# LM317_3S_LithiumCharger_2018_05_13.net
KiCad netlist of a schematic drawn in EAGLE
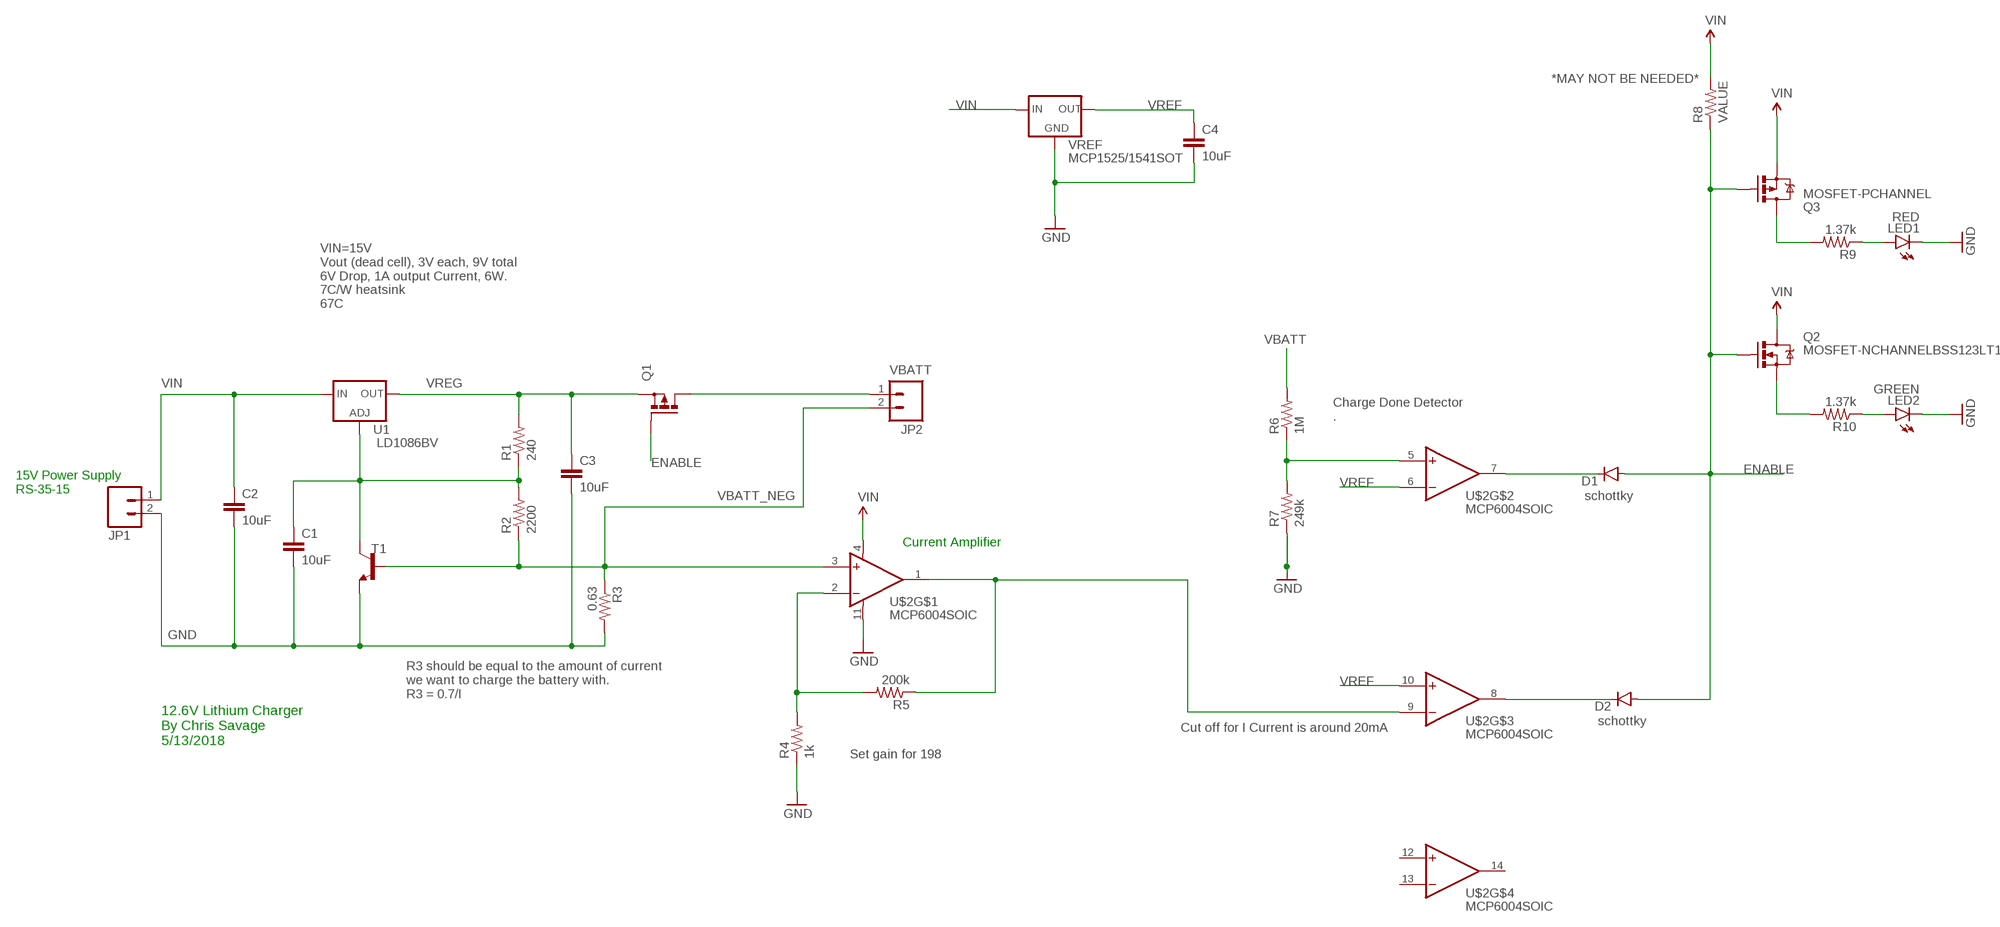
[diagram p0: schematic, sheet 1]

(export (version "E")
  (design (tool "Eeschema 10.0.6"))
  (components
    (comp (ref "C1")
      (value "10uF")
      (footprint "eagle-import:1206")
      (libsource (lib "eagle-import") (part "CAP1206"))
    )
    (comp (ref "C2")
      (value "10uF")
      (footprint "eagle-import:1206")
      (libsource (lib "eagle-import") (part "CAP1206"))
    )
    (comp (ref "C3")
      (value "10uF")
      (footprint "eagle-import:1206")
      (libsource (lib "eagle-import") (part "CAP1206"))
    )
    (comp (ref "C4")
      (value "10uF")
      (footprint "eagle-import:1206")
      (libsource (lib "eagle-import") (part "CAP1206"))
    )
    (comp (ref "D1")
      (value "DIODESOD123")
      (footprint "eagle-import:SOD-123")
      (libsource (lib "eagle-import") (part "DIODESOD123"))
    )
    (comp (ref "D2")
      (value "DIODESOD123")
      (footprint "eagle-import:SOD-123")
      (libsource (lib "eagle-import") (part "DIODESOD123"))
    )
    (comp (ref "JP1")
      (value "M02POLAR_LOCK")
      (footprint "eagle-import:MOLEX-1X2_LOCK")
      (libsource (lib "eagle-import") (part "M02POLAR_LOCK"))
    )
    (comp (ref "JP2")
      (value "M02POLAR_LOCK")
      (footprint "eagle-import:MOLEX-1X2_LOCK")
      (libsource (lib "eagle-import") (part "M02POLAR_LOCK"))
    )
    (comp (ref "LED1")
      (value "RED")
      (footprint "eagle-import:LED5MM")
      (libsource (lib "eagle-import") (part "LED5MM"))
    )
    (comp (ref "LED2")
      (value "GREEN")
      (footprint "eagle-import:LED5MM")
      (libsource (lib "eagle-import") (part "LED5MM"))
    )
    (comp (ref "Q1")
      (value "PMOSFET_PTO220BV")
      (footprint "eagle-import:TO220BV")
      (libsource (lib "eagle-import") (part "PMOSFET_PTO220BV"))
    )
    (comp (ref "Q2")
      (value "MOSFET-NCHANNELBSS123LT1G")
      (footprint "eagle-import:SOT23-3")
      (libsource (lib "eagle-import") (part "MOSFET-NCHANNELBSS123LT1G"))
    )
    (comp (ref "Q3")
      (value "MOSFET-PCHANNEL")
      (footprint "eagle-import:SOT23-3")
      (libsource (lib "eagle-import") (part "MOSFET-PCHANNEL"))
    )
    (comp (ref "R1")
      (value "240")
      (footprint "eagle-import:1206")
      (libsource (lib "eagle-import") (part "RESISTOR1206"))
    )
    (comp (ref "R2")
      (value "2200")
      (footprint "eagle-import:1206")
      (libsource (lib "eagle-import") (part "RESISTOR1206"))
    )
    (comp (ref "R3")
      (value "0.63")
      (footprint "eagle-import:R2512")
      (libsource (lib "eagle-import") (part "RESISTOR2512"))
    )
    (comp (ref "R4")
      (value "1k")
      (footprint "eagle-import:1206")
      (libsource (lib "eagle-import") (part "RESISTOR1206"))
    )
    (comp (ref "R5")
      (value "200k")
      (footprint "eagle-import:1206")
      (libsource (lib "eagle-import") (part "RESISTOR1206"))
    )
    (comp (ref "R6")
      (value "1M")
      (footprint "eagle-import:1206")
      (libsource (lib "eagle-import") (part "RESISTOR1206"))
    )
    (comp (ref "R7")
      (value "249k")
      (footprint "eagle-import:1206")
      (libsource (lib "eagle-import") (part "RESISTOR1206"))
    )
    (comp (ref "R8")
      (value "VALUE")
      (footprint "eagle-import:1206")
      (libsource (lib "eagle-import") (part "RESISTOR1206"))
    )
    (comp (ref "R9")
      (value "1.37k")
      (footprint "eagle-import:1206")
      (libsource (lib "eagle-import") (part "RESISTOR1206"))
    )
    (comp (ref "R10")
      (value "1.37k")
      (footprint "eagle-import:1206")
      (libsource (lib "eagle-import") (part "RESISTOR1206"))
    )
    (comp (ref "T1")
      (value "MMBT3904LT1-NPN-SOT23-BEC")
      (footprint "eagle-import:SOT23-BEC")
      (libsource (lib "eagle-import") (part "-NPN-SOT23-BECMMBT3904LT1"))
    )
    (comp (ref "U$2")
      (value "MCP6004SOIC")
      (footprint "eagle-import:SOIC-14")
      (libsource (lib "eagle-import") (part "MCP6004SOIC"))
    )
    (comp (ref "U1")
      (value "LD1086BV")
      (footprint "eagle-import:317TS")
      (libsource (lib "eagle-import") (part "LM317TS"))
    )
    (comp (ref "VREF")
      (value "MCP1525/1541SOT")
      (footprint "eagle-import:SOT23-3")
      (libsource (lib "eagle-import") (part "MCP1525/1541SOT"))
    )
  )
  (nets
    (net (code "1") (name "/ENABLE") (class "Default")
      (node (ref "D1") (pin "A") (pinfunction "A_A") (pintype "passive"))
      (node (ref "D2") (pin "A") (pinfunction "A_A") (pintype "passive"))
      (node (ref "Q1") (pin "G") (pinfunction "G_G") (pintype "passive"))
      (node (ref "Q2") (pin "1") (pinfunction "G_1") (pintype "passive"))
      (node (ref "Q3") (pin "1") (pinfunction "G_1") (pintype "passive"))
      (node (ref "R8") (pin "1") (pinfunction "1_1") (pintype "passive"))
    )
    (net (code "2") (name "/VBATT") (class "Default")
      (node (ref "JP2") (pin "1") (pinfunction "1_1") (pintype "passive"))
      (node (ref "Q1") (pin "D") (pinfunction "D_D") (pintype "passive"))
      (node (ref "R6") (pin "2") (pinfunction "2_2") (pintype "passive"))
    )
    (net (code "3") (name "/VBATT_NEG") (class "Default")
      (node (ref "JP2") (pin "2") (pinfunction "2_2") (pintype "passive"))
      (node (ref "R2") (pin "1") (pinfunction "1_1") (pintype "passive"))
      (node (ref "R3") (pin "1") (pinfunction "1_1") (pintype "passive"))
      (node (ref "T1") (pin "B") (pinfunction "B_B") (pintype "passive"))
      (node (ref "U$2") (pin "3") (pinfunction "+IN_3") (pintype "input"))
    )
    (net (code "4") (name "/VREF") (class "Default")
      (node (ref "C4") (pin "1") (pinfunction "1_1") (pintype "passive"))
      (node (ref "U$2") (pin "10") (pinfunction "+IN_10") (pintype "input"))
      (node (ref "U$2") (pin "6") (pinfunction "-IN_6") (pintype "input"))
      (node (ref "VREF") (pin "2") (pinfunction "OUT_2") (pintype "output"))
    )
    (net (code "5") (name "/VREG") (class "Default")
      (node (ref "C3") (pin "1") (pinfunction "1_1") (pintype "passive"))
      (node (ref "Q1") (pin "S") (pinfunction "S_S") (pintype "passive"))
      (node (ref "R1") (pin "2") (pinfunction "2_2") (pintype "passive"))
      (node (ref "U1") (pin "2") (pinfunction "OUT_2") (pintype "passive"))
    )
    (net (code "6") (name "GND") (class "Default")
      (node (ref "C1") (pin "2") (pinfunction "2_2") (pintype "passive"))
      (node (ref "C2") (pin "2") (pinfunction "2_2") (pintype "passive"))
      (node (ref "C3") (pin "2") (pinfunction "2_2") (pintype "passive"))
      (node (ref "C4") (pin "2") (pinfunction "2_2") (pintype "passive"))
      (node (ref "JP1") (pin "2") (pinfunction "2_2") (pintype "passive"))
      (node (ref "LED1") (pin "K") (pinfunction "C_K") (pintype "passive"))
      (node (ref "LED2") (pin "K") (pinfunction "C_K") (pintype "passive"))
      (node (ref "R3") (pin "2") (pinfunction "2_2") (pintype "passive"))
      (node (ref "R4") (pin "1") (pinfunction "1_1") (pintype "passive"))
      (node (ref "R7") (pin "1") (pinfunction "1_1") (pintype "passive"))
      (node (ref "T1") (pin "E") (pinfunction "E_E") (pintype "passive"))
      (node (ref "U$2") (pin "11") (pinfunction "V-_11") (pintype "power_in"))
      (node (ref "VREF") (pin "3") (pinfunction "GND_3") (pintype "input"))
    )
    (net (code "7") (name "Net-(LED1-PadA)") (class "Default")
      (node (ref "LED1") (pin "A") (pinfunction "A_A") (pintype "passive"))
      (node (ref "R9") (pin "1") (pinfunction "1_1") (pintype "passive"))
    )
    (net (code "8") (name "Net-(LED2-PadA)") (class "Default")
      (node (ref "LED2") (pin "A") (pinfunction "A_A") (pintype "passive"))
      (node (ref "R10") (pin "1") (pinfunction "1_1") (pintype "passive"))
    )
    (net (code "9") (name "Net-(Q2-S)") (class "Default")
      (node (ref "Q2") (pin "2") (pinfunction "S_2") (pintype "passive"))
      (node (ref "R10") (pin "2") (pinfunction "2_2") (pintype "passive"))
    )
    (net (code "10") (name "Net-(Q3-D)") (class "Default")
      (node (ref "Q3") (pin "3") (pinfunction "D_3") (pintype "passive"))
      (node (ref "R9") (pin "2") (pinfunction "2_2") (pintype "passive"))
    )
    (net (code "11") (name "Net-(U$2A--IN)") (class "Default")
      (node (ref "R4") (pin "2") (pinfunction "2_2") (pintype "passive"))
      (node (ref "R5") (pin "2") (pinfunction "2_2") (pintype "passive"))
      (node (ref "U$2") (pin "2") (pinfunction "-IN_2") (pintype "input"))
    )
    (net (code "12") (name "Net-(U$2A-OUT)") (class "Default")
      (node (ref "R5") (pin "1") (pinfunction "1_1") (pintype "passive"))
      (node (ref "U$2") (pin "1") (pinfunction "OUT_1") (pintype "output"))
      (node (ref "U$2") (pin "9") (pinfunction "-IN_9") (pintype "input"))
    )
    (net (code "13") (name "Net-(U$2B-+IN)") (class "Default")
      (node (ref "R6") (pin "1") (pinfunction "1_1") (pintype "passive"))
      (node (ref "R7") (pin "2") (pinfunction "2_2") (pintype "passive"))
      (node (ref "U$2") (pin "5") (pinfunction "+IN_5") (pintype "input"))
    )
    (net (code "14") (name "Net-(U$2B-OUT)") (class "Default")
      (node (ref "D1") (pin "C") (pinfunction "C_C") (pintype "passive"))
      (node (ref "U$2") (pin "7") (pinfunction "OUT_7") (pintype "output"))
    )
    (net (code "15") (name "Net-(U$2C-OUT)") (class "Default")
      (node (ref "D2") (pin "C") (pinfunction "C_C") (pintype "passive"))
      (node (ref "U$2") (pin "8") (pinfunction "OUT_8") (pintype "output"))
    )
    (net (code "16") (name "Net-(U1-ADJ)") (class "Default")
      (node (ref "C1") (pin "1") (pinfunction "1_1") (pintype "passive"))
      (node (ref "R1") (pin "1") (pinfunction "1_1") (pintype "passive"))
      (node (ref "R2") (pin "2") (pinfunction "2_2") (pintype "passive"))
      (node (ref "T1") (pin "C") (pinfunction "C_C") (pintype "passive"))
      (node (ref "U1") (pin "1") (pinfunction "ADJ_1") (pintype "input"))
    )
    (net (code "17") (name "VIN") (class "Default")
      (node (ref "C2") (pin "1") (pinfunction "1_1") (pintype "passive"))
      (node (ref "JP1") (pin "1") (pinfunction "1_1") (pintype "passive"))
      (node (ref "Q2") (pin "3") (pinfunction "D_3") (pintype "passive"))
      (node (ref "Q3") (pin "2") (pinfunction "S_2") (pintype "passive"))
      (node (ref "R8") (pin "2") (pinfunction "2_2") (pintype "passive"))
      (node (ref "U$2") (pin "4") (pinfunction "V+_4") (pintype "power_in"))
      (node (ref "U1") (pin "3") (pinfunction "IN_3") (pintype "input"))
      (node (ref "VREF") (pin "1") (pinfunction "IN_1") (pintype "input"))
    )
    (net (code "18") (name "unconnected-(U$2D-+IN-Pad12)") (class "Default")
      (node (ref "U$2") (pin "12") (pinfunction "+IN_12") (pintype "input"))
    )
    (net (code "19") (name "unconnected-(U$2D--IN-Pad13)") (class "Default")
      (node (ref "U$2") (pin "13") (pinfunction "-IN_13") (pintype "input"))
    )
    (net (code "20") (name "unconnected-(U$2D-OUT-Pad14)") (class "Default")
      (node (ref "U$2") (pin "14") (pinfunction "OUT_14") (pintype "output"))
    )
  )
)
